# ssslidar_v0_1_blade_PWR.net
KiCad netlist of a schematic drawn in EAGLE
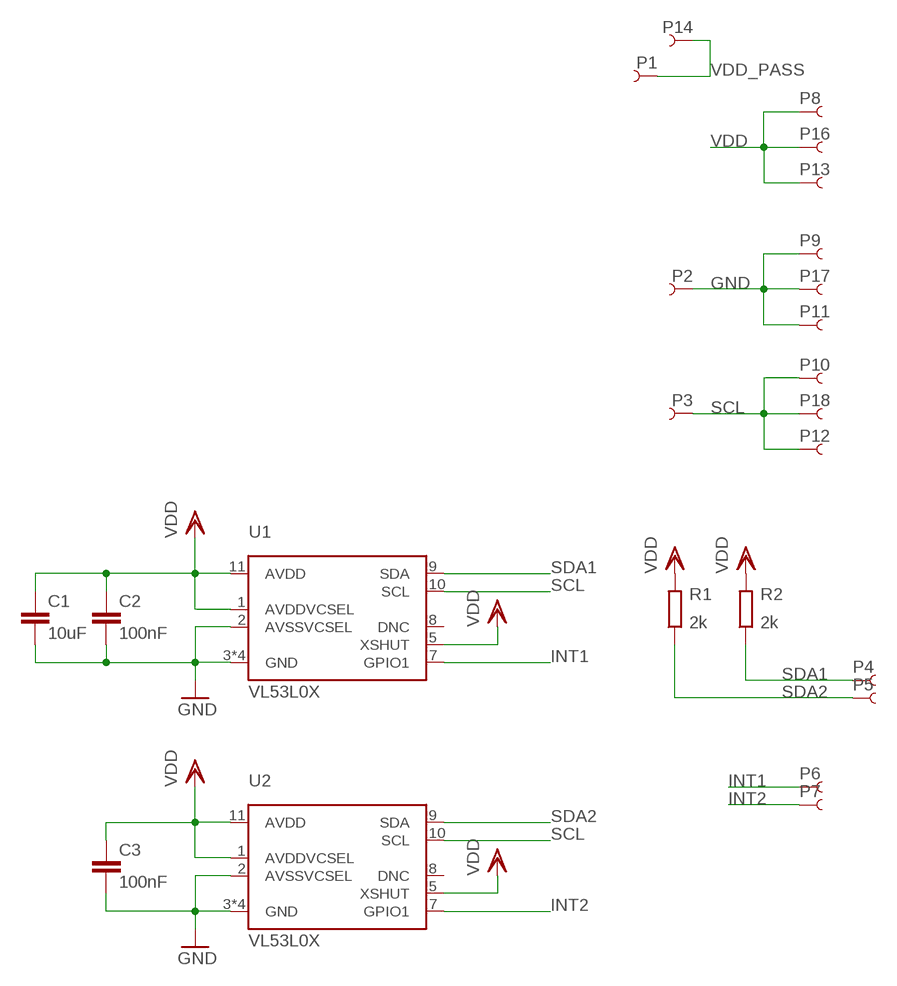
[diagram p0: schematic, sheet 1]

(export (version "E")
  (design (tool "Eeschema 10.0.6"))
  (components
    (comp (ref "C1")
      (value "10uF")
      (footprint "eagle-import:0805_N")
      (libsource (lib "eagle-import") (part "C0805"))
    )
    (comp (ref "C2")
      (value "100nF")
      (footprint "eagle-import:0402_N")
      (libsource (lib "eagle-import") (part "C0402"))
    )
    (comp (ref "C3")
      (value "100nF")
      (footprint "eagle-import:0402_N")
      (libsource (lib "eagle-import") (part "C0402"))
    )
    (comp (ref "P1")
      (value "PIN_SMD_0.8X1_RECT")
      (footprint "eagle-import:PIN_SMD_0.8X1_RECT")
      (libsource (lib "eagle-import") (part "PIN_SMD_0.8X1_RECT"))
    )
    (comp (ref "P2")
      (value "PIN_SMD_1X1_RECT")
      (footprint "eagle-import:PIN_SMD_1X1_RECT")
      (libsource (lib "eagle-import") (part "PIN_SMD_1X1_RECT"))
    )
    (comp (ref "P3")
      (value "PIN_SMD_0.8X1_RECT")
      (footprint "eagle-import:PIN_SMD_0.8X1_RECT")
      (libsource (lib "eagle-import") (part "PIN_SMD_0.8X1_RECT"))
    )
    (comp (ref "P4")
      (value "PIN_SMD_0.8X1_RECT")
      (footprint "eagle-import:PIN_SMD_0.8X1_RECT")
      (libsource (lib "eagle-import") (part "PIN_SMD_0.8X1_RECT"))
    )
    (comp (ref "P5")
      (value "PIN_SMD_0.8X1_RECT")
      (footprint "eagle-import:PIN_SMD_0.8X1_RECT")
      (libsource (lib "eagle-import") (part "PIN_SMD_0.8X1_RECT"))
    )
    (comp (ref "P6")
      (value "PIN_SMD_0.8X1_RECT")
      (footprint "eagle-import:PIN_SMD_0.8X1_RECT")
      (libsource (lib "eagle-import") (part "PIN_SMD_0.8X1_RECT"))
    )
    (comp (ref "P7")
      (value "PIN_SMD_0.8X1_RECT")
      (footprint "eagle-import:PIN_SMD_0.8X1_RECT")
      (libsource (lib "eagle-import") (part "PIN_SMD_0.8X1_RECT"))
    )
    (comp (ref "P8")
      (value "PIN_SMD_0.8X1_RECT")
      (footprint "eagle-import:PIN_SMD_0.8X1_RECT")
      (libsource (lib "eagle-import") (part "PIN_SMD_0.8X1_RECT"))
    )
    (comp (ref "P9")
      (value "PIN_SMD_1X1_RECT")
      (footprint "eagle-import:PIN_SMD_1X1_RECT")
      (libsource (lib "eagle-import") (part "PIN_SMD_1X1_RECT"))
    )
    (comp (ref "P10")
      (value "PIN_SMD_0.8X1_RECT")
      (footprint "eagle-import:PIN_SMD_0.8X1_RECT")
      (libsource (lib "eagle-import") (part "PIN_SMD_0.8X1_RECT"))
    )
    (comp (ref "P11")
      (value "PIN_SMD_1X1_RECT")
      (footprint "eagle-import:PIN_SMD_1X1_RECT")
      (libsource (lib "eagle-import") (part "PIN_SMD_1X1_RECT"))
    )
    (comp (ref "P12")
      (value "PIN_SMD_0.8X1_RECT")
      (footprint "eagle-import:PIN_SMD_0.8X1_RECT")
      (libsource (lib "eagle-import") (part "PIN_SMD_0.8X1_RECT"))
    )
    (comp (ref "P13")
      (value "PIN_SMD_0.8X1_RECT")
      (footprint "eagle-import:PIN_SMD_0.8X1_RECT")
      (libsource (lib "eagle-import") (part "PIN_SMD_0.8X1_RECT"))
    )
    (comp (ref "P14")
      (value "PIN_SMD_0.8X1_RECT")
      (footprint "eagle-import:PIN_SMD_0.8X1_RECT")
      (libsource (lib "eagle-import") (part "PIN_SMD_0.8X1_RECT"))
    )
    (comp (ref "P16")
      (value "PIN_SMD_0.8X1_RECT")
      (footprint "eagle-import:PIN_SMD_0.8X1_RECT")
      (libsource (lib "eagle-import") (part "PIN_SMD_0.8X1_RECT"))
    )
    (comp (ref "P17")
      (value "PIN_SMD_1X1_RECT")
      (footprint "eagle-import:PIN_SMD_1X1_RECT")
      (libsource (lib "eagle-import") (part "PIN_SMD_1X1_RECT"))
    )
    (comp (ref "P18")
      (value "PIN_SMD_0.8X1_RECT")
      (footprint "eagle-import:PIN_SMD_0.8X1_RECT")
      (libsource (lib "eagle-import") (part "PIN_SMD_0.8X1_RECT"))
    )
    (comp (ref "R1")
      (value "2k")
      (footprint "eagle-import:0402_N")
      (libsource (lib "eagle-import") (part "R0402"))
    )
    (comp (ref "R2")
      (value "2k")
      (footprint "eagle-import:0402_N")
      (libsource (lib "eagle-import") (part "R0402"))
    )
    (comp (ref "U1")
      (value "VL53L0X")
      (footprint "eagle-import:VL53L0X")
      (libsource (lib "eagle-import") (part "VL53L0X"))
    )
    (comp (ref "U2")
      (value "VL53L0X")
      (footprint "eagle-import:VL53L0X")
      (libsource (lib "eagle-import") (part "VL53L0X"))
    )
  )
  (nets
    (net (code "1") (name "/INT1") (class "Default")
      (node (ref "P6") (pin "PIN") (pinfunction "1_PIN") (pintype "bidirectional"))
      (node (ref "U1") (pin "7") (pinfunction "GPIO1_7") (pintype "bidirectional"))
    )
    (net (code "2") (name "/INT2") (class "Default")
      (node (ref "P7") (pin "PIN") (pinfunction "1_PIN") (pintype "bidirectional"))
      (node (ref "U2") (pin "7") (pinfunction "GPIO1_7") (pintype "bidirectional"))
    )
    (net (code "3") (name "/SCL") (class "Default")
      (node (ref "P10") (pin "PIN") (pinfunction "1_PIN") (pintype "bidirectional"))
      (node (ref "P12") (pin "PIN") (pinfunction "1_PIN") (pintype "bidirectional"))
      (node (ref "P18") (pin "PIN") (pinfunction "1_PIN") (pintype "bidirectional"))
      (node (ref "P3") (pin "PIN") (pinfunction "1_PIN") (pintype "bidirectional"))
      (node (ref "U1") (pin "10") (pinfunction "SCL_10") (pintype "bidirectional"))
      (node (ref "U2") (pin "10") (pinfunction "SCL_10") (pintype "bidirectional"))
    )
    (net (code "4") (name "/SDA1") (class "Default")
      (node (ref "P4") (pin "PIN") (pinfunction "1_PIN") (pintype "bidirectional"))
      (node (ref "R2") (pin "1") (pinfunction "1_1") (pintype "passive"))
      (node (ref "U1") (pin "9") (pinfunction "SDA_9") (pintype "bidirectional"))
    )
    (net (code "5") (name "/SDA2") (class "Default")
      (node (ref "P5") (pin "PIN") (pinfunction "1_PIN") (pintype "bidirectional"))
      (node (ref "R1") (pin "1") (pinfunction "1_1") (pintype "passive"))
      (node (ref "U2") (pin "9") (pinfunction "SDA_9") (pintype "bidirectional"))
    )
    (net (code "6") (name "/VDD_PASS") (class "Default")
      (node (ref "P1") (pin "PIN") (pinfunction "1_PIN") (pintype "bidirectional"))
      (node (ref "P14") (pin "PIN") (pinfunction "1_PIN") (pintype "bidirectional"))
    )
    (net (code "7") (name "GND") (class "Default")
      (node (ref "C1") (pin "2") (pinfunction "2_2") (pintype "passive"))
      (node (ref "C2") (pin "2") (pinfunction "2_2") (pintype "passive"))
      (node (ref "C3") (pin "2") (pinfunction "2_2") (pintype "passive"))
      (node (ref "P11") (pin "PIN") (pinfunction "1_PIN") (pintype "bidirectional"))
      (node (ref "P17") (pin "PIN") (pinfunction "1_PIN") (pintype "bidirectional"))
      (node (ref "P2") (pin "PIN") (pinfunction "1_PIN") (pintype "bidirectional"))
      (node (ref "P9") (pin "PIN") (pinfunction "1_PIN") (pintype "bidirectional"))
      (node (ref "U1") (pin "12") (pinfunction "GND_12") (pintype "bidirectional"))
      (node (ref "U1") (pin "2") (pinfunction "AVSSVCSEL_2") (pintype "bidirectional"))
      (node (ref "U1") (pin "3") (pinfunction "GND_3") (pintype "bidirectional"))
      (node (ref "U1") (pin "4") (pinfunction "GND_4") (pintype "bidirectional"))
      (node (ref "U1") (pin "6") (pinfunction "GND_6") (pintype "bidirectional"))
      (node (ref "U2") (pin "12") (pinfunction "GND_12") (pintype "bidirectional"))
      (node (ref "U2") (pin "2") (pinfunction "AVSSVCSEL_2") (pintype "bidirectional"))
      (node (ref "U2") (pin "3") (pinfunction "GND_3") (pintype "bidirectional"))
      (node (ref "U2") (pin "4") (pinfunction "GND_4") (pintype "bidirectional"))
      (node (ref "U2") (pin "6") (pinfunction "GND_6") (pintype "bidirectional"))
    )
    (net (code "8") (name "VDD") (class "Default")
      (node (ref "C1") (pin "1") (pinfunction "1_1") (pintype "passive"))
      (node (ref "C2") (pin "1") (pinfunction "1_1") (pintype "passive"))
      (node (ref "C3") (pin "1") (pinfunction "1_1") (pintype "passive"))
      (node (ref "P13") (pin "PIN") (pinfunction "1_PIN") (pintype "bidirectional"))
      (node (ref "P16") (pin "PIN") (pinfunction "1_PIN") (pintype "bidirectional"))
      (node (ref "P8") (pin "PIN") (pinfunction "1_PIN") (pintype "bidirectional"))
      (node (ref "R1") (pin "2") (pinfunction "2_2") (pintype "passive"))
      (node (ref "R2") (pin "2") (pinfunction "2_2") (pintype "passive"))
      (node (ref "U1") (pin "1") (pinfunction "AVDDVCSEL_1") (pintype "bidirectional"))
      (node (ref "U1") (pin "11") (pinfunction "AVDD_11") (pintype "bidirectional"))
      (node (ref "U1") (pin "5") (pinfunction "XSHUT_5") (pintype "bidirectional"))
      (node (ref "U2") (pin "1") (pinfunction "AVDDVCSEL_1") (pintype "bidirectional"))
      (node (ref "U2") (pin "11") (pinfunction "AVDD_11") (pintype "bidirectional"))
      (node (ref "U2") (pin "5") (pinfunction "XSHUT_5") (pintype "bidirectional"))
    )
    (net (code "9") (name "unconnected-(U1-DNC-Pad8)") (class "Default")
      (node (ref "U1") (pin "8") (pinfunction "DNC_8") (pintype "bidirectional"))
    )
    (net (code "10") (name "unconnected-(U2-DNC-Pad8)") (class "Default")
      (node (ref "U2") (pin "8") (pinfunction "DNC_8") (pintype "bidirectional"))
    )
  )
)
